# HDMI.net
KiCad netlist of a schematic drawn in Altium Designer
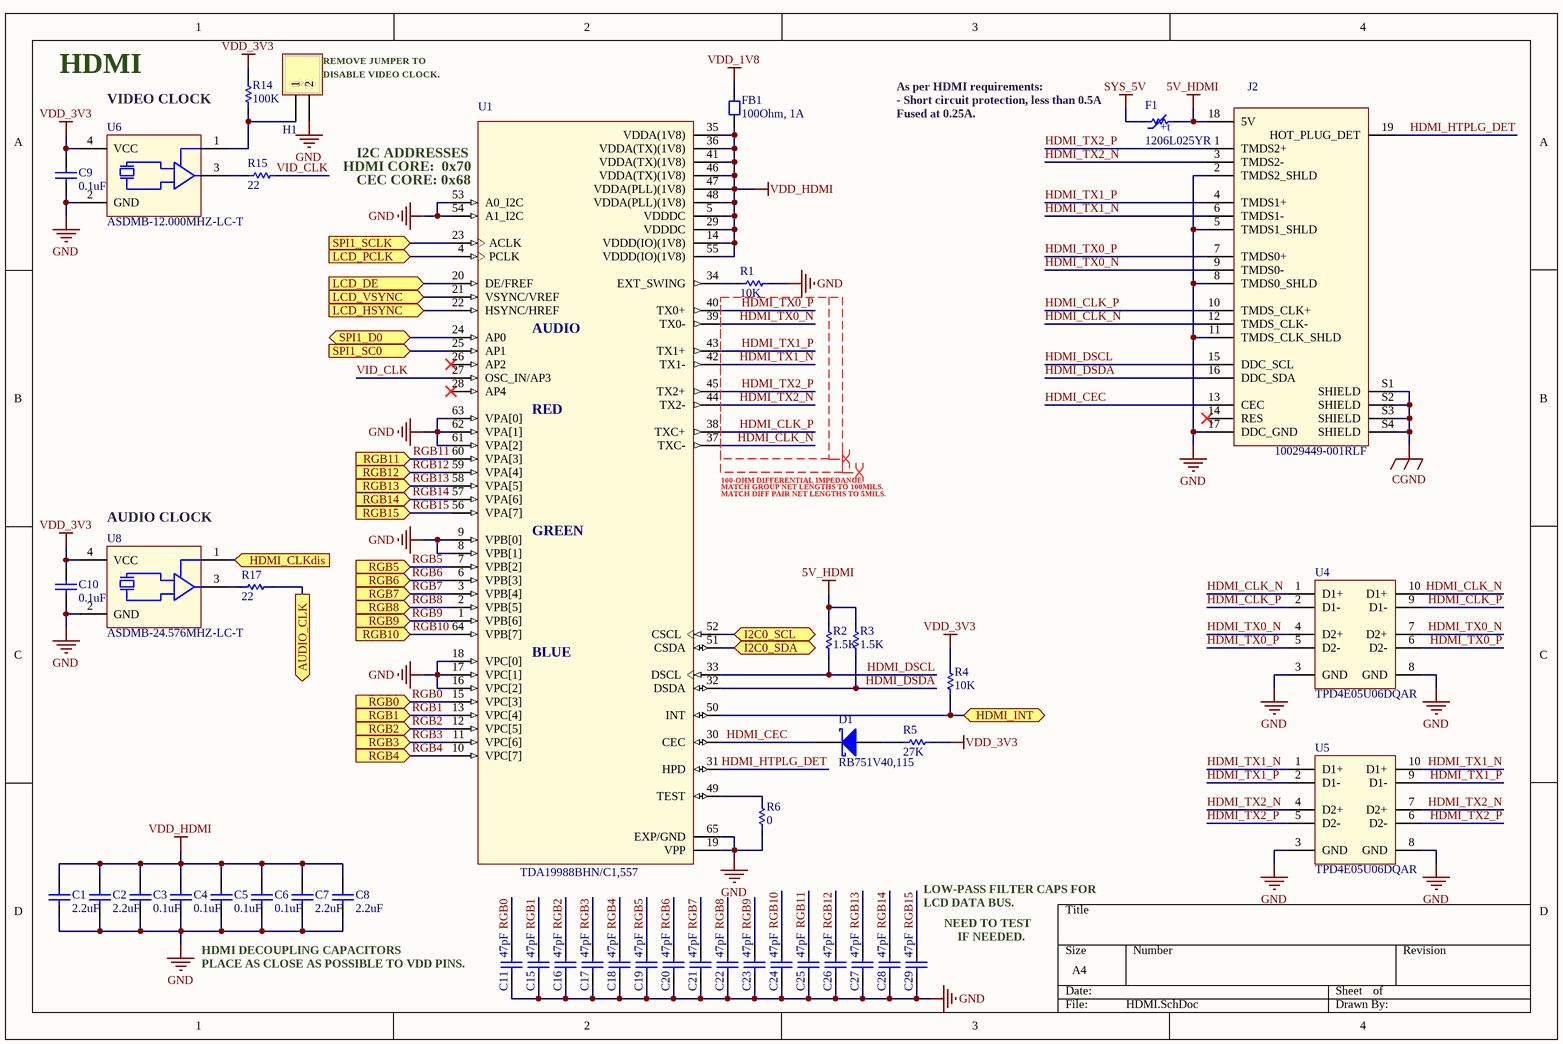
[diagram p0: HDMI.SchDoc]

(export (version "E")
  (design (tool "Eeschema 10.0.6"))
  (components
    (comp (ref "C1")
      (value "2.2uF")
      (footprint "CAP_0603")
      (description "CAP CER 2.2UF 16V X5R 0603")
      (fields (field (name "MANUFACTURER") "KEMET") (field (name "MANUFACTURER PART NO.") "C0603C104M4RACTU"))
      (libsource (lib "OSD335-X_Devboard") (part "C0603C225M4PAC7867"))
    )
    (comp (ref "C2")
      (value "2.2uF")
      (footprint "CAP_0603")
      (description "CAP CER 2.2UF 16V X5R 0603")
      (fields (field (name "MANUFACTURER") "KEMET") (field (name "MANUFACTURER PART NO.") "C0603C104M4RACTU"))
      (libsource (lib "OSD335-X_Devboard") (part "C0603C225M4PAC7867"))
    )
    (comp (ref "C3")
      (value "0.1uF")
      (footprint "CAP_0603")
      (description "CAP CER 0.1UF 16V X7R 0603")
      (fields (field (name "MANUFACTURER") "KEMET") (field (name "MANUFACTURER PART NO.") "C0603C104M4RACTU"))
      (libsource (lib "OSD335-X_Devboard") (part "C0603C104M4RACTU"))
    )
    (comp (ref "C4")
      (value "0.1uF")
      (footprint "CAP_0603")
      (description "CAP CER 0.1UF 16V X7R 0603")
      (fields (field (name "MANUFACTURER") "KEMET") (field (name "MANUFACTURER PART NO.") "C0603C104M4RACTU"))
      (libsource (lib "OSD335-X_Devboard") (part "C0603C104M4RACTU"))
    )
    (comp (ref "C5")
      (value "0.1uF")
      (footprint "CAP_0603")
      (description "CAP CER 0.1UF 16V X7R 0603")
      (fields (field (name "MANUFACTURER") "KEMET") (field (name "MANUFACTURER PART NO.") "C0603C104M4RACTU"))
      (libsource (lib "OSD335-X_Devboard") (part "C0603C104M4RACTU"))
    )
    (comp (ref "C6")
      (value "0.1uF")
      (footprint "CAP_0603")
      (description "CAP CER 0.1UF 16V X7R 0603")
      (fields (field (name "MANUFACTURER") "KEMET") (field (name "MANUFACTURER PART NO.") "C0603C104M4RACTU"))
      (libsource (lib "OSD335-X_Devboard") (part "C0603C104M4RACTU"))
    )
    (comp (ref "C7")
      (value "2.2uF")
      (footprint "CAP_0603")
      (description "CAP CER 2.2UF 16V X5R 0603")
      (fields (field (name "MANUFACTURER") "KEMET") (field (name "MANUFACTURER PART NO.") "C0603C104M4RACTU"))
      (libsource (lib "OSD335-X_Devboard") (part "C0603C225M4PAC7867"))
    )
    (comp (ref "C8")
      (value "2.2uF")
      (footprint "CAP_0603")
      (description "CAP CER 2.2UF 16V X5R 0603")
      (fields (field (name "MANUFACTURER") "KEMET") (field (name "MANUFACTURER PART NO.") "C0603C104M4RACTU"))
      (libsource (lib "OSD335-X_Devboard") (part "C0603C225M4PAC7867"))
    )
    (comp (ref "C9")
      (value "0.1uF")
      (footprint "CAP_0603")
      (description "CAP CER 0.1UF 16V X7R 0603")
      (fields (field (name "MANUFACTURER") "KEMET") (field (name "MANUFACTURER PART NO.") "C0603C104M4RACTU"))
      (libsource (lib "OSD335-X_Devboard") (part "C0603C104M4RACTU"))
    )
    (comp (ref "C10")
      (value "0.1uF")
      (footprint "CAP_0603")
      (description "CAP CER 0.1UF 16V X7R 0603")
      (fields (field (name "MANUFACTURER") "KEMET") (field (name "MANUFACTURER PART NO.") "C0603C104M4RACTU"))
      (libsource (lib "OSD335-X_Devboard") (part "C0603C104M4RACTU"))
    )
    (comp (ref "C11")
      (value "47pF")
      (footprint "CAP_0402")
      (description "CAP CER 47PF 10V C0G/NP0 0402")
      (fields
        (field (name "MANUFACTURER PART NO.") "885012005011")
        (field (name "MANUFACTURER") "Wurth Elektronik")
      )
      (libsource (lib "OSD335-X_Devboard") (part "885012005011"))
    )
    (comp (ref "C15")
      (value "47pF")
      (footprint "CAP_0402")
      (description "CAP CER 47PF 10V C0G/NP0 0402")
      (fields
        (field (name "MANUFACTURER PART NO.") "885012005011")
        (field (name "MANUFACTURER") "Wurth Elektronik")
      )
      (libsource (lib "OSD335-X_Devboard") (part "885012005011"))
    )
    (comp (ref "C16")
      (value "47pF")
      (footprint "CAP_0402")
      (description "CAP CER 47PF 10V C0G/NP0 0402")
      (fields
        (field (name "MANUFACTURER PART NO.") "885012005011")
        (field (name "MANUFACTURER") "Wurth Elektronik")
      )
      (libsource (lib "OSD335-X_Devboard") (part "885012005011"))
    )
    (comp (ref "C17")
      (value "47pF")
      (footprint "CAP_0402")
      (description "CAP CER 47PF 10V C0G/NP0 0402")
      (fields
        (field (name "MANUFACTURER PART NO.") "885012005011")
        (field (name "MANUFACTURER") "Wurth Elektronik")
      )
      (libsource (lib "OSD335-X_Devboard") (part "885012005011"))
    )
    (comp (ref "C18")
      (value "47pF")
      (footprint "CAP_0402")
      (description "CAP CER 47PF 10V C0G/NP0 0402")
      (fields
        (field (name "MANUFACTURER PART NO.") "885012005011")
        (field (name "MANUFACTURER") "Wurth Elektronik")
      )
      (libsource (lib "OSD335-X_Devboard") (part "885012005011"))
    )
    (comp (ref "C19")
      (value "47pF")
      (footprint "CAP_0402")
      (description "CAP CER 47PF 10V C0G/NP0 0402")
      (fields
        (field (name "MANUFACTURER PART NO.") "885012005011")
        (field (name "MANUFACTURER") "Wurth Elektronik")
      )
      (libsource (lib "OSD335-X_Devboard") (part "885012005011"))
    )
    (comp (ref "C20")
      (value "47pF")
      (footprint "CAP_0402")
      (description "CAP CER 47PF 10V C0G/NP0 0402")
      (fields
        (field (name "MANUFACTURER PART NO.") "885012005011")
        (field (name "MANUFACTURER") "Wurth Elektronik")
      )
      (libsource (lib "OSD335-X_Devboard") (part "885012005011"))
    )
    (comp (ref "C21")
      (value "47pF")
      (footprint "CAP_0402")
      (description "CAP CER 47PF 10V C0G/NP0 0402")
      (fields
        (field (name "MANUFACTURER PART NO.") "885012005011")
        (field (name "MANUFACTURER") "Wurth Elektronik")
      )
      (libsource (lib "OSD335-X_Devboard") (part "885012005011"))
    )
    (comp (ref "C22")
      (value "47pF")
      (footprint "CAP_0402")
      (description "CAP CER 47PF 10V C0G/NP0 0402")
      (fields
        (field (name "MANUFACTURER PART NO.") "885012005011")
        (field (name "MANUFACTURER") "Wurth Elektronik")
      )
      (libsource (lib "OSD335-X_Devboard") (part "885012005011"))
    )
    (comp (ref "C23")
      (value "47pF")
      (footprint "CAP_0402")
      (description "CAP CER 47PF 10V C0G/NP0 0402")
      (fields
        (field (name "MANUFACTURER PART NO.") "885012005011")
        (field (name "MANUFACTURER") "Wurth Elektronik")
      )
      (libsource (lib "OSD335-X_Devboard") (part "885012005011"))
    )
    (comp (ref "C24")
      (value "47pF")
      (footprint "CAP_0402")
      (description "CAP CER 47PF 10V C0G/NP0 0402")
      (fields
        (field (name "MANUFACTURER PART NO.") "885012005011")
        (field (name "MANUFACTURER") "Wurth Elektronik")
      )
      (libsource (lib "OSD335-X_Devboard") (part "885012005011"))
    )
    (comp (ref "C25")
      (value "47pF")
      (footprint "CAP_0402")
      (description "CAP CER 47PF 10V C0G/NP0 0402")
      (fields
        (field (name "MANUFACTURER PART NO.") "885012005011")
        (field (name "MANUFACTURER") "Wurth Elektronik")
      )
      (libsource (lib "OSD335-X_Devboard") (part "885012005011"))
    )
    (comp (ref "C26")
      (value "47pF")
      (footprint "CAP_0402")
      (description "CAP CER 47PF 10V C0G/NP0 0402")
      (fields
        (field (name "MANUFACTURER PART NO.") "885012005011")
        (field (name "MANUFACTURER") "Wurth Elektronik")
      )
      (libsource (lib "OSD335-X_Devboard") (part "885012005011"))
    )
    (comp (ref "C27")
      (value "47pF")
      (footprint "CAP_0402")
      (description "CAP CER 47PF 10V C0G/NP0 0402")
      (fields
        (field (name "MANUFACTURER PART NO.") "885012005011")
        (field (name "MANUFACTURER") "Wurth Elektronik")
      )
      (libsource (lib "OSD335-X_Devboard") (part "885012005011"))
    )
    (comp (ref "C28")
      (value "47pF")
      (footprint "CAP_0402")
      (description "CAP CER 47PF 10V C0G/NP0 0402")
      (fields
        (field (name "MANUFACTURER PART NO.") "885012005011")
        (field (name "MANUFACTURER") "Wurth Elektronik")
      )
      (libsource (lib "OSD335-X_Devboard") (part "885012005011"))
    )
    (comp (ref "C29")
      (value "47pF")
      (footprint "CAP_0402")
      (description "CAP CER 47PF 10V C0G/NP0 0402")
      (fields
        (field (name "MANUFACTURER PART NO.") "885012005011")
        (field (name "MANUFACTURER") "Wurth Elektronik")
      )
      (libsource (lib "OSD335-X_Devboard") (part "885012005011"))
    )
    (comp (ref "D1")
      (value "RB751V40,115")
      (footprint "SOD-323")
      (description "DIODE SCHOTTKY 40V 120MA SOD323")
      (fields (field (name "MANUFACTURER") "Nexperia USA Inc."))
      (libsource (lib "OSD335-X_Devboard") (part "RB751V40,115"))
    )
    (comp (ref "F1")
      (value "1206L025YR")
      (footprint "RES_1206")
      (description "PTC RESET FUSE 16V 250MA 1206")
      (fields (field (name "MANUFACTURER") "Littelfuse Inc."))
      (libsource (lib "OSD335-X_Devboard") (part "1206L025YR"))
    )
    (comp (ref "FB1")
      (value "100Ohm, 1A")
      (footprint "CAP_0603")
      (description "FERRITE BEAD 100 OHM 0603 1LN")
      (fields
        (field (name "MANUFACTURER PART NO.") "MPZ1608D101BTA00")
        (field (name "MANUFACTURER") "TDK Corporation")
      )
      (libsource (lib "OSD335-X_Devboard") (part "MPZ1608D101BTA00"))
    )
    (comp (ref "H1")
      (value "02p")
      (footprint "HEADER_2X1_2.54MM")
      (description "CONN HEADER VERT 2POS 2.54MM")
      (fields
        (field (name "MANUFACTURER") "Wurth Elektronik")
        (field (name "MANUFACTURER PART NO.") "61300211121")
      )
      (libsource (lib "OSD335-X_Devboard") (part "61300211121"))
    )
    (comp (ref "J2")
      (value "10029449-001RLF")
      (footprint "10029449-001RLF")
      (description "CONN RCPT 1.4 HDMI 19POS SMD R/A")
      (fields (field (name "MANUFACTURER") "Amphenol ICC (FCI)"))
      (libsource (lib "OSD335-X_Devboard") (part "10029449-001RLF"))
    )
    (comp (ref "R1")
      (value "10K")
      (footprint "RES_0603")
      (description "RES SMD 10K OHM 1% 1/10W 0603")
      (fields (field (name "TOLERANCE") "1%") (field (name "MANUFACTURER") "Yageo"))
      (libsource (lib "OSD335-X_Devboard") (part "RC0603FR-0710KL"))
    )
    (comp (ref "R2")
      (value "1.5K")
      (footprint "RES_0603")
      (description "RES SMD 1.5K OHM 1% 1/10W 0603")
      (fields (field (name "TOLERANCE") "1%") (field (name "MANUFACTURER") "Yageo"))
      (libsource (lib "OSD335-X_Devboard") (part "RC0603FR-071K5L"))
    )
    (comp (ref "R3")
      (value "1.5K")
      (footprint "RES_0603")
      (description "RES SMD 1.5K OHM 1% 1/10W 0603")
      (fields (field (name "TOLERANCE") "1%") (field (name "MANUFACTURER") "Yageo"))
      (libsource (lib "OSD335-X_Devboard") (part "RC0603FR-071K5L"))
    )
    (comp (ref "R4")
      (value "10K")
      (footprint "RES_0603")
      (description "RES SMD 10K OHM 1% 1/10W 0603")
      (fields (field (name "TOLERANCE") "1%") (field (name "MANUFACTURER") "Yageo"))
      (libsource (lib "OSD335-X_Devboard") (part "RC0603FR-0710KL"))
    )
    (comp (ref "R5")
      (value "27K")
      (footprint "RES_0603")
      (description "RES SMD 27K OHM 1% 1/10W 0603")
      (fields (field (name "TOLERANCE") "1%") (field (name "MANUFACTURER") "Yageo"))
      (libsource (lib "OSD335-X_Devboard") (part "RC0603FR-0727KL"))
    )
    (comp (ref "R6")
      (value "0")
      (footprint "RES_0603")
      (description "RES SMD 0 OHM JUMPER 1/10W 0603")
      (fields (field (name "MANUFACTURER") "Yageo") (field (name "MANUFACTURER PART NO.") "RC0603JR-070RL"))
      (libsource (lib "OSD335-X_Devboard") (part "RC0603JR-070RL"))
    )
    (comp (ref "R14")
      (value "100K")
      (footprint "RES_0603")
      (description "RES SMD 100K OHM 1% 1/10W 0603")
      (fields (field (name "TOLERANCE") "1%") (field (name "MANUFACTURER") "Yageo"))
      (libsource (lib "OSD335-X_Devboard") (part "RC0603FR-07100KL"))
    )
    (comp (ref "R15")
      (value "22")
      (footprint "RES_0603")
      (description "RES SMD 22 OHM 5% 1/10W 0603")
      (fields (field (name "TOLERANCE") "5%") (field (name "MANUFACTURER") "Yageo"))
      (libsource (lib "OSD335-X_Devboard") (part "RC0603JR-0722RL"))
    )
    (comp (ref "R17")
      (value "22")
      (footprint "RES_0603")
      (description "RES SMD 22 OHM 5% 1/10W 0603")
      (fields (field (name "TOLERANCE") "5%") (field (name "MANUFACTURER") "Yageo"))
      (libsource (lib "OSD335-X_Devboard") (part "RC0603JR-0722RL"))
    )
    (comp (ref "U1")
      (value "TDA19988BHN/C1,557")
      (footprint "HVQFN-64_9x9MM")
      (description "IC VIDEO HDMI TRANS 64HVQFN")
      (fields (field (name "MANUFACTURER") "NXP USA Inc."))
      (libsource (lib "OSD335-X_Devboard") (part "TDA19988BHN"))
    )
    (comp (ref "U4")
      (value "TPD4E05U06DQAR")
      (footprint "USON-10_2.5X1MM")
      (description "TVS DIODE 5.5V 14V 10SON")
      (fields (field (name "MANUFACTURER") "Texas Instruments"))
      (libsource (lib "OSD335-X_Devboard") (part "TPD4E05U06DQAR"))
    )
    (comp (ref "U5")
      (value "TPD4E05U06DQAR")
      (footprint "USON-10_2.5X1MM")
      (description "TVS DIODE 5.5V 14V 10SON")
      (fields (field (name "MANUFACTURER") "Texas Instruments"))
      (libsource (lib "OSD335-X_Devboard") (part "TPD4E05U06DQAR"))
    )
    (comp (ref "U6")
      (value "ASDMB-12.000MHZ-LC-T")
      (footprint "ABRACON_4SMD_QFN")
      (description "MEMS OSC XO 12.0000MHZ LVCMOS")
      (fields (field (name "MANUFACTURER") "Abracon LLC"))
      (libsource (lib "OSD335-X_Devboard") (part "ASDMB-12.000MHZ-LC-T"))
    )
    (comp (ref "U8")
      (value "ASDMB-24.576MHZ-LC-T")
      (footprint "ABRACON_4SMD_QFN")
      (description "MEMS OSC XO 24.5760MHZ LVCMOS")
      (fields (field (name "MANUFACTURER") "Abracon LLC"))
      (libsource (lib "OSD335-X_Devboard") (part "ASDMB-24.576MHZ-LC-T"))
    )
  )
  (nets
    (net (code "1") (name "/AUDIO_CLK") (class "Default")
      (node (ref "R17") (pin "2") (pinfunction "2_2") (pintype "passive"))
    )
    (net (code "2") (name "/HDMI_CEC") (class "Default")
      (node (ref "D1") (pin "2") (pinfunction "K_2") (pintype "passive"))
      (node (ref "J2") (pin "13") (pinfunction "CEC_13") (pintype "passive"))
      (node (ref "U1") (pin "30") (pinfunction "CEC_30") (pintype "bidirectional"))
    )
    (net (code "3") (name "/HDMI_CLK_N") (class "Default")
      (node (ref "J2") (pin "12") (pinfunction "TMDS_CLK-_12") (pintype "passive"))
      (node (ref "U1") (pin "37") (pinfunction "TXC-_37") (pintype "output"))
      (node (ref "U4") (pin "1") (pinfunction "D1+_1") (pintype "passive"))
      (node (ref "U4") (pin "10") (pinfunction "D1+_10") (pintype "passive"))
    )
    (net (code "4") (name "/HDMI_CLK_P") (class "Default")
      (node (ref "J2") (pin "10") (pinfunction "TMDS_CLK+_10") (pintype "passive"))
      (node (ref "U1") (pin "38") (pinfunction "TXC+_38") (pintype "output"))
      (node (ref "U4") (pin "2") (pinfunction "D1-_2") (pintype "passive"))
      (node (ref "U4") (pin "9") (pinfunction "D1-_9") (pintype "passive"))
    )
    (net (code "5") (name "/HDMI_CLKdis") (class "Default")
      (node (ref "U8") (pin "1") (pinfunction "STDBY_1") (pintype "passive"))
    )
    (net (code "6") (name "/HDMI_DSCL") (class "Default")
      (node (ref "J2") (pin "15") (pinfunction "DDC_SCL_15") (pintype "passive"))
      (node (ref "R2") (pin "1") (pinfunction "1_1") (pintype "passive"))
      (node (ref "U1") (pin "33") (pinfunction "DSCL_33") (pintype "input"))
    )
    (net (code "7") (name "/HDMI_DSDA") (class "Default")
      (node (ref "J2") (pin "16") (pinfunction "DDC_SDA_16") (pintype "passive"))
      (node (ref "R3") (pin "1") (pinfunction "1_1") (pintype "passive"))
      (node (ref "U1") (pin "32") (pinfunction "DSDA_32") (pintype "bidirectional"))
    )
    (net (code "8") (name "/HDMI_HTPLG_DET") (class "Default")
      (node (ref "J2") (pin "19") (pinfunction "HOT_PLUG_DET_19") (pintype "passive"))
      (node (ref "U1") (pin "31") (pinfunction "HPD_31") (pintype "bidirectional"))
    )
    (net (code "9") (name "/HDMI_INT") (class "Default")
      (node (ref "R4") (pin "1") (pinfunction "1_1") (pintype "passive"))
      (node (ref "U1") (pin "50") (pinfunction "INT_50") (pintype "bidirectional"))
    )
    (net (code "10") (name "/HDMI_TX0_N") (class "Default")
      (node (ref "J2") (pin "9") (pinfunction "TMDS0-_9") (pintype "passive"))
      (node (ref "U1") (pin "39") (pinfunction "TX0-_39") (pintype "output"))
      (node (ref "U4") (pin "4") (pinfunction "D2+_4") (pintype "passive"))
      (node (ref "U4") (pin "7") (pinfunction "D2+_7") (pintype "passive"))
    )
    (net (code "11") (name "/HDMI_TX0_P") (class "Default")
      (node (ref "J2") (pin "7") (pinfunction "TMDS0+_7") (pintype "passive"))
      (node (ref "U1") (pin "40") (pinfunction "TX0+_40") (pintype "output"))
      (node (ref "U4") (pin "5") (pinfunction "D2-_5") (pintype "passive"))
      (node (ref "U4") (pin "6") (pinfunction "D2-_6") (pintype "passive"))
    )
    (net (code "12") (name "/HDMI_TX1_N") (class "Default")
      (node (ref "J2") (pin "6") (pinfunction "TMDS1-_6") (pintype "passive"))
      (node (ref "U1") (pin "42") (pinfunction "TX1-_42") (pintype "output"))
      (node (ref "U5") (pin "1") (pinfunction "D1+_1") (pintype "passive"))
      (node (ref "U5") (pin "10") (pinfunction "D1+_10") (pintype "passive"))
    )
    (net (code "13") (name "/HDMI_TX1_P") (class "Default")
      (node (ref "J2") (pin "4") (pinfunction "TMDS1+_4") (pintype "passive"))
      (node (ref "U1") (pin "43") (pinfunction "TX1+_43") (pintype "output"))
      (node (ref "U5") (pin "2") (pinfunction "D1-_2") (pintype "passive"))
      (node (ref "U5") (pin "9") (pinfunction "D1-_9") (pintype "passive"))
    )
    (net (code "14") (name "/HDMI_TX2_N") (class "Default")
      (node (ref "J2") (pin "3") (pinfunction "TMDS2-_3") (pintype "passive"))
      (node (ref "U1") (pin "44") (pinfunction "TX2-_44") (pintype "output"))
      (node (ref "U5") (pin "4") (pinfunction "D2+_4") (pintype "passive"))
      (node (ref "U5") (pin "7") (pinfunction "D2+_7") (pintype "passive"))
    )
    (net (code "15") (name "/HDMI_TX2_P") (class "Default")
      (node (ref "J2") (pin "1") (pinfunction "TMDS2+_1") (pintype "passive"))
      (node (ref "U1") (pin "45") (pinfunction "TX2+_45") (pintype "output"))
      (node (ref "U5") (pin "5") (pinfunction "D2-_5") (pintype "passive"))
      (node (ref "U5") (pin "6") (pinfunction "D2-_6") (pintype "passive"))
    )
    (net (code "16") (name "/I2C0_SCL") (class "Default")
      (node (ref "U1") (pin "52") (pinfunction "CSCL_52") (pintype "input"))
    )
    (net (code "17") (name "/I2C0_SDA") (class "Default")
      (node (ref "U1") (pin "51") (pinfunction "CSDA_51") (pintype "bidirectional"))
    )
    (net (code "18") (name "/LCD_DE") (class "Default")
      (node (ref "U1") (pin "20") (pinfunction "DE/FREF_20") (pintype "input"))
    )
    (net (code "19") (name "/LCD_HSYNC") (class "Default")
      (node (ref "U1") (pin "22") (pinfunction "HSYNC/HREF_22") (pintype "input"))
    )
    (net (code "20") (name "/LCD_PCLK") (class "Default")
      (node (ref "U1") (pin "4") (pinfunction "PCLK_4") (pintype "input"))
    )
    (net (code "21") (name "/LCD_VSYNC") (class "Default")
      (node (ref "U1") (pin "21") (pinfunction "VSYNC/VREF_21") (pintype "input"))
    )
    (net (code "22") (name "/RGB0") (class "Default")
      (node (ref "C11") (pin "2") (pinfunction "P_2") (pintype "passive"))
      (node (ref "U1") (pin "15") (pinfunction "VPC[3]_15") (pintype "input"))
    )
    (net (code "23") (name "/RGB1") (class "Default")
      (node (ref "C15") (pin "2") (pinfunction "P_2") (pintype "passive"))
      (node (ref "U1") (pin "13") (pinfunction "VPC[4]_13") (pintype "input"))
    )
    (net (code "24") (name "/RGB2") (class "Default")
      (node (ref "C16") (pin "2") (pinfunction "P_2") (pintype "passive"))
      (node (ref "U1") (pin "12") (pinfunction "VPC[5]_12") (pintype "input"))
    )
    (net (code "25") (name "/RGB3") (class "Default")
      (node (ref "C17") (pin "2") (pinfunction "P_2") (pintype "passive"))
      (node (ref "U1") (pin "11") (pinfunction "VPC[6]_11") (pintype "input"))
    )
    (net (code "26") (name "/RGB4") (class "Default")
      (node (ref "C18") (pin "2") (pinfunction "P_2") (pintype "passive"))
      (node (ref "U1") (pin "10") (pinfunction "VPC[7]_10") (pintype "input"))
    )
    (net (code "27") (name "/RGB5") (class "Default")
      (node (ref "C19") (pin "2") (pinfunction "P_2") (pintype "passive"))
      (node (ref "U1") (pin "7") (pinfunction "VPB[2]_7") (pintype "input"))
    )
    (net (code "28") (name "/RGB6") (class "Default")
      (node (ref "C20") (pin "2") (pinfunction "P_2") (pintype "passive"))
      (node (ref "U1") (pin "6") (pinfunction "VPB[3]_6") (pintype "input"))
    )
    (net (code "29") (name "/RGB7") (class "Default")
      (node (ref "C21") (pin "2") (pinfunction "P_2") (pintype "passive"))
      (node (ref "U1") (pin "3") (pinfunction "VPB[4]_3") (pintype "input"))
    )
    (net (code "30") (name "/RGB8") (class "Default")
      (node (ref "C22") (pin "2") (pinfunction "P_2") (pintype "passive"))
      (node (ref "U1") (pin "2") (pinfunction "VPB[5]_2") (pintype "input"))
    )
    (net (code "31") (name "/RGB9") (class "Default")
      (node (ref "C23") (pin "2") (pinfunction "P_2") (pintype "passive"))
      (node (ref "U1") (pin "1") (pinfunction "VPB[6]_1") (pintype "input"))
    )
    (net (code "32") (name "/RGB10") (class "Default")
      (node (ref "C24") (pin "2") (pinfunction "P_2") (pintype "passive"))
      (node (ref "U1") (pin "64") (pinfunction "VPB[7]_64") (pintype "input"))
    )
    (net (code "33") (name "/RGB11") (class "Default")
      (node (ref "C25") (pin "2") (pinfunction "P_2") (pintype "passive"))
      (node (ref "U1") (pin "60") (pinfunction "VPA[3]_60") (pintype "input"))
    )
    (net (code "34") (name "/RGB12") (class "Default")
      (node (ref "C26") (pin "2") (pinfunction "P_2") (pintype "passive"))
      (node (ref "U1") (pin "59") (pinfunction "VPA[4]_59") (pintype "input"))
    )
    (net (code "35") (name "/RGB13") (class "Default")
      (node (ref "C27") (pin "2") (pinfunction "P_2") (pintype "passive"))
      (node (ref "U1") (pin "58") (pinfunction "VPA[5]_58") (pintype "input"))
    )
    (net (code "36") (name "/RGB14") (class "Default")
      (node (ref "C28") (pin "2") (pinfunction "P_2") (pintype "passive"))
      (node (ref "U1") (pin "57") (pinfunction "VPA[6]_57") (pintype "input"))
    )
    (net (code "37") (name "/RGB15") (class "Default")
      (node (ref "C29") (pin "2") (pinfunction "P_2") (pintype "passive"))
      (node (ref "U1") (pin "56") (pinfunction "VPA[7]_56") (pintype "input"))
    )
    (net (code "38") (name "/SPI1_D0") (class "Default")
      (node (ref "U1") (pin "24") (pinfunction "AP0_24") (pintype "input"))
    )
    (net (code "39") (name "/SPI1_SC0") (class "Default")
      (node (ref "U1") (pin "25") (pinfunction "AP1_25") (pintype "input"))
    )
    (net (code "40") (name "/SPI1_SCLK") (class "Default")
      (node (ref "U1") (pin "23") (pinfunction "ACLK_23") (pintype "input"))
    )
    (net (code "41") (name "/VID_CLK") (class "Default")
      (node (ref "R15") (pin "2") (pinfunction "2_2") (pintype "passive"))
      (node (ref "U1") (pin "27") (pinfunction "OSC_IN/AP3_27") (pintype "input"))
    )
    (net (code "42") (name "5V_HDMI") (class "Default")
      (node (ref "F1") (pin "2") (pinfunction "2_2") (pintype "passive"))
      (node (ref "J2") (pin "18") (pinfunction "5V_18") (pintype "passive"))
      (node (ref "R2") (pin "2") (pinfunction "2_2") (pintype "passive"))
      (node (ref "R3") (pin "2") (pinfunction "2_2") (pintype "passive"))
    )
    (net (code "43") (name "CGND") (class "Default")
      (node (ref "J2") (pin "S1") (pinfunction "SHIELD_S1") (pintype "passive"))
      (node (ref "J2") (pin "S2") (pinfunction "SHIELD_S2") (pintype "passive"))
      (node (ref "J2") (pin "S3") (pinfunction "SHIELD_S3") (pintype "passive"))
      (node (ref "J2") (pin "S4") (pinfunction "SHIELD_S4") (pintype "passive"))
    )
    (net (code "44") (name "GND") (class "Default")
      (node (ref "C1") (pin "1") (pinfunction "1_1") (pintype "passive"))
      (node (ref "C10") (pin "1") (pinfunction "1_1") (pintype "passive"))
      (node (ref "C11") (pin "1") (pinfunction "N_1") (pintype "passive"))
      (node (ref "C15") (pin "1") (pinfunction "N_1") (pintype "passive"))
      (node (ref "C16") (pin "1") (pinfunction "N_1") (pintype "passive"))
      (node (ref "C17") (pin "1") (pinfunction "N_1") (pintype "passive"))
      (node (ref "C18") (pin "1") (pinfunction "N_1") (pintype "passive"))
      (node (ref "C19") (pin "1") (pinfunction "N_1") (pintype "passive"))
      (node (ref "C2") (pin "1") (pinfunction "1_1") (pintype "passive"))
      (node (ref "C20") (pin "1") (pinfunction "N_1") (pintype "passive"))
      (node (ref "C21") (pin "1") (pinfunction "N_1") (pintype "passive"))
      (node (ref "C22") (pin "1") (pinfunction "N_1") (pintype "passive"))
      (node (ref "C23") (pin "1") (pinfunction "N_1") (pintype "passive"))
      (node (ref "C24") (pin "1") (pinfunction "N_1") (pintype "passive"))
      (node (ref "C25") (pin "1") (pinfunction "N_1") (pintype "passive"))
      (node (ref "C26") (pin "1") (pinfunction "N_1") (pintype "passive"))
      (node (ref "C27") (pin "1") (pinfunction "N_1") (pintype "passive"))
      (node (ref "C28") (pin "1") (pinfunction "N_1") (pintype "passive"))
      (node (ref "C29") (pin "1") (pinfunction "N_1") (pintype "passive"))
      (node (ref "C3") (pin "1") (pinfunction "1_1") (pintype "passive"))
      (node (ref "C4") (pin "1") (pinfunction "1_1") (pintype "passive"))
      (node (ref "C5") (pin "1") (pinfunction "1_1") (pintype "passive"))
      (node (ref "C6") (pin "1") (pinfunction "1_1") (pintype "passive"))
      (node (ref "C7") (pin "1") (pinfunction "1_1") (pintype "passive"))
      (node (ref "C8") (pin "1") (pinfunction "1_1") (pintype "passive"))
      (node (ref "C9") (pin "1") (pinfunction "1_1") (pintype "passive"))
      (node (ref "H1") (pin "2") (pinfunction "2_2") (pintype "passive"))
      (node (ref "J2") (pin "11") (pinfunction "TMDS_CLK_SHLD_11") (pintype "passive"))
      (node (ref "J2") (pin "17") (pinfunction "DDC_GND_17") (pintype "passive"))
      (node (ref "J2") (pin "2") (pinfunction "TMDS2_SHLD_2") (pintype "passive"))
      (node (ref "J2") (pin "5") (pinfunction "TMDS1_SHLD_5") (pintype "passive"))
      (node (ref "J2") (pin "8") (pinfunction "TMDS0_SHLD_8") (pintype "passive"))
      (node (ref "R1") (pin "1") (pinfunction "1_1") (pintype "passive"))
      (node (ref "R6") (pin "1") (pinfunction "1_1") (pintype "passive"))
      (node (ref "U1") (pin "16") (pinfunction "VPC[2]_16") (pintype "input"))
      (node (ref "U1") (pin "17") (pinfunction "VPC[1]_17") (pintype "input"))
      (node (ref "U1") (pin "18") (pinfunction "VPC[0]_18") (pintype "input"))
      (node (ref "U1") (pin "19") (pinfunction "VPP_19") (pintype "power_in"))
      (node (ref "U1") (pin "53") (pinfunction "A0_I2C_53") (pintype "input"))
      (node (ref "U1") (pin "54") (pinfunction "A1_I2C_54") (pintype "input"))
      (node (ref "U1") (pin "61") (pinfunction "VPA[2]_61") (pintype "input"))
      (node (ref "U1") (pin "62") (pinfunction "VPA[1]_62") (pintype "input"))
      (node (ref "U1") (pin "63") (pinfunction "VPA[0]_63") (pintype "input"))
      (node (ref "U1") (pin "65") (pinfunction "EXP/GND_65") (pintype "power_in"))
      (node (ref "U1") (pin "8") (pinfunction "VPB[1]_8") (pintype "input"))
      (node (ref "U1") (pin "9") (pinfunction "VPB[0]_9") (pintype "input"))
      (node (ref "U4") (pin "3") (pinfunction "GND_3") (pintype "passive"))
      (node (ref "U4") (pin "8") (pinfunction "GND_8") (pintype "passive"))
      (node (ref "U5") (pin "3") (pinfunction "GND_3") (pintype "passive"))
      (node (ref "U5") (pin "8") (pinfunction "GND_8") (pintype "passive"))
      (node (ref "U6") (pin "2") (pinfunction "GND_2") (pintype "passive"))
      (node (ref "U8") (pin "2") (pinfunction "GND_2") (pintype "passive"))
    )
    (net (code "45") (name "Net-(D1-A)") (class "Default")
      (node (ref "D1") (pin "1") (pinfunction "A_1") (pintype "passive"))
      (node (ref "R5") (pin "1") (pinfunction "1_1") (pintype "passive"))
    )
    (net (code "46") (name "Net-(U1-EXT_SWING)") (class "Default")
      (node (ref "R1") (pin "2") (pinfunction "2_2") (pintype "passive"))
      (node (ref "U1") (pin "34") (pinfunction "EXT_SWING_34") (pintype "output"))
    )
    (net (code "47") (name "Net-(U1-TEST)") (class "Default")
      (node (ref "R6") (pin "2") (pinfunction "2_2") (pintype "passive"))
      (node (ref "U1") (pin "49") (pinfunction "TEST_49") (pintype "bidirectional"))
    )
    (net (code "48") (name "Net-(U6-OUT)") (class "Default")
      (node (ref "R15") (pin "1") (pinfunction "1_1") (pintype "passive"))
      (node (ref "U6") (pin "3") (pinfunction "OUT_3") (pintype "passive"))
    )
    (net (code "49") (name "Net-(U6-STDBY)") (class "Default")
      (node (ref "H1") (pin "1") (pinfunction "1_1") (pintype "passive"))
      (node (ref "R14") (pin "1") (pinfunction "1_1") (pintype "passive"))
      (node (ref "U6") (pin "1") (pinfunction "STDBY_1") (pintype "passive"))
    )
    (net (code "50") (name "Net-(U8-OUT)") (class "Default")
      (node (ref "R17") (pin "1") (pinfunction "1_1") (pintype "passive"))
      (node (ref "U8") (pin "3") (pinfunction "OUT_3") (pintype "passive"))
    )
    (net (code "51") (name "SYS_5V") (class "Default")
      (node (ref "F1") (pin "1") (pinfunction "1_1") (pintype "passive"))
    )
    (net (code "52") (name "VDD_1V8") (class "Default")
      (node (ref "FB1") (pin "2") (pinfunction "2_2") (pintype "passive"))
    )
    (net (code "53") (name "VDD_3V3") (class "Default")
      (node (ref "C10") (pin "2") (pinfunction "2_2") (pintype "passive"))
      (node (ref "C9") (pin "2") (pinfunction "2_2") (pintype "passive"))
      (node (ref "R14") (pin "2") (pinfunction "2_2") (pintype "passive"))
      (node (ref "R4") (pin "2") (pinfunction "2_2") (pintype "passive"))
      (node (ref "R5") (pin "2") (pinfunction "2_2") (pintype "passive"))
      (node (ref "U6") (pin "4") (pinfunction "VCC_4") (pintype "passive"))
      (node (ref "U8") (pin "4") (pinfunction "VCC_4") (pintype "passive"))
    )
    (net (code "54") (name "VDD_HDMI") (class "Default")
      (node (ref "C1") (pin "2") (pinfunction "2_2") (pintype "passive"))
      (node (ref "C2") (pin "2") (pinfunction "2_2") (pintype "passive"))
      (node (ref "C3") (pin "2") (pinfunction "2_2") (pintype "passive"))
      (node (ref "C4") (pin "2") (pinfunction "2_2") (pintype "passive"))
      (node (ref "C5") (pin "2") (pinfunction "2_2") (pintype "passive"))
      (node (ref "C6") (pin "2") (pinfunction "2_2") (pintype "passive"))
      (node (ref "C7") (pin "2") (pinfunction "2_2") (pintype "passive"))
      (node (ref "C8") (pin "2") (pinfunction "2_2") (pintype "passive"))
      (node (ref "FB1") (pin "1") (pinfunction "1_1") (pintype "passive"))
      (node (ref "U1") (pin "14") (pinfunction "VDDD(IO)(1V8)_14") (pintype "power_in"))
      (node (ref "U1") (pin "29") (pinfunction "VDDDC_29") (pintype "power_in"))
      (node (ref "U1") (pin "35") (pinfunction "VDDA(1V8)_35") (pintype "power_in"))
      (node (ref "U1") (pin "36") (pinfunction "VDDA(TX)(1V8)_36") (pintype "power_in"))
      (node (ref "U1") (pin "41") (pinfunction "VDDA(TX)(1V8)_41") (pintype "power_in"))
      (node (ref "U1") (pin "46") (pinfunction "VDDA(TX)(1V8)_46") (pintype "power_in"))
      (node (ref "U1") (pin "47") (pinfunction "VDDA(PLL)(1V8)_47") (pintype "power_in"))
      (node (ref "U1") (pin "48") (pinfunction "VDDA(PLL)(1V8)_48") (pintype "power_in"))
      (node (ref "U1") (pin "5") (pinfunction "VDDDC_5") (pintype "power_in"))
      (node (ref "U1") (pin "55") (pinfunction "VDDD(IO)(1V8)_55") (pintype "power_in"))
    )
    (net (code "55") (name "unconnected-(J2-RES-Pad14)") (class "Default")
      (node (ref "J2") (pin "14") (pinfunction "RES_14") (pintype "passive+no_connect"))
    )
    (net (code "56") (name "unconnected-(U1-AP2-Pad26)") (class "Default")
      (node (ref "U1") (pin "26") (pinfunction "AP2_26") (pintype "input+no_connect"))
    )
    (net (code "57") (name "unconnected-(U1-AP4-Pad28)") (class "Default")
      (node (ref "U1") (pin "28") (pinfunction "AP4_28") (pintype "input+no_connect"))
    )
  )
)
